# manual4.net
KiCad netlist of a schematic drawn in EAGLE
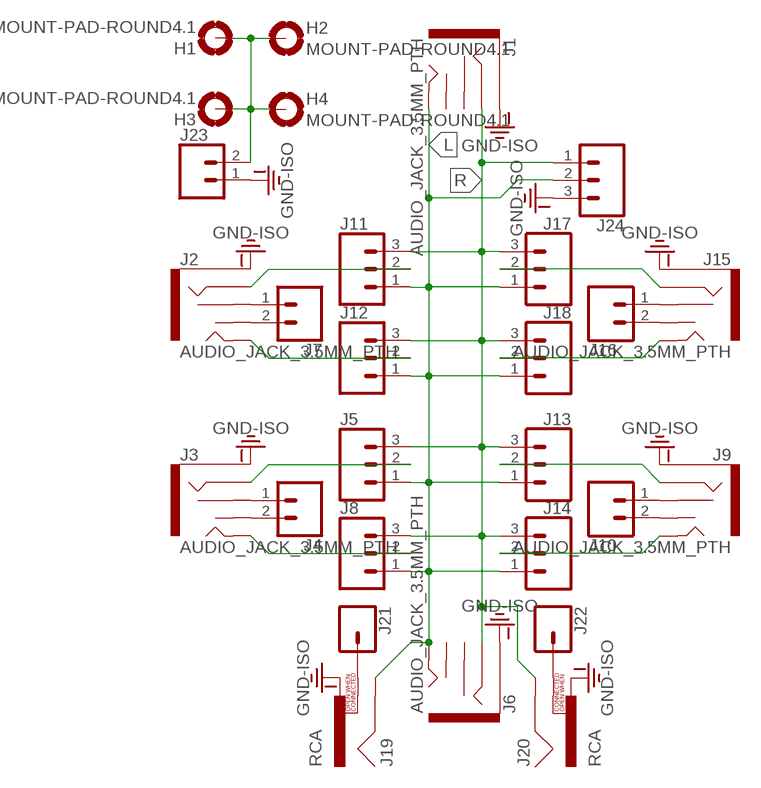
[diagram p0: schematic, sheet 1]

(export (version "E")
  (design (tool "Eeschema 10.0.6"))
  (components
    (comp (ref "H1")
      (value "MOUNT-PAD-ROUND4.1")
      (footprint "eagle-import:4,1-PAD")
      (libsource (lib "eagle-import") (part "MOUNT-PAD-ROUND4.1"))
    )
    (comp (ref "H2")
      (value "MOUNT-PAD-ROUND4.1")
      (footprint "eagle-import:4,1-PAD")
      (libsource (lib "eagle-import") (part "MOUNT-PAD-ROUND4.1"))
    )
    (comp (ref "H3")
      (value "MOUNT-PAD-ROUND4.1")
      (footprint "eagle-import:4,1-PAD")
      (libsource (lib "eagle-import") (part "MOUNT-PAD-ROUND4.1"))
    )
    (comp (ref "H4")
      (value "MOUNT-PAD-ROUND4.1")
      (footprint "eagle-import:4,1-PAD")
      (libsource (lib "eagle-import") (part "MOUNT-PAD-ROUND4.1"))
    )
    (comp (ref "J1")
      (value "AUDIO_JACK_3.5MM_PTH")
      (footprint "eagle-import:AUDIO-JACK")
      (libsource (lib "eagle-import") (part "AUDIO_JACK_3.5MM_PTH"))
    )
    (comp (ref "J2")
      (value "AUDIO_JACK_3.5MM_PTH")
      (footprint "eagle-import:AUDIO-JACK")
      (libsource (lib "eagle-import") (part "AUDIO_JACK_3.5MM_PTH"))
    )
    (comp (ref "J3")
      (value "AUDIO_JACK_3.5MM_PTH")
      (footprint "eagle-import:AUDIO-JACK")
      (libsource (lib "eagle-import") (part "AUDIO_JACK_3.5MM_PTH"))
    )
    (comp (ref "J4")
      (value "CONN_02")
      (footprint "eagle-import:1X02")
      (libsource (lib "eagle-import") (part "CONN_02"))
    )
    (comp (ref "J5")
      (value "CONN_03")
      (footprint "eagle-import:1X03")
      (libsource (lib "eagle-import") (part "CONN_03"))
    )
    (comp (ref "J6")
      (value "AUDIO_JACK_3.5MM_PTH")
      (footprint "eagle-import:AUDIO-JACK")
      (libsource (lib "eagle-import") (part "AUDIO_JACK_3.5MM_PTH"))
    )
    (comp (ref "J7")
      (value "CONN_02")
      (footprint "eagle-import:1X02")
      (libsource (lib "eagle-import") (part "CONN_02"))
    )
    (comp (ref "J8")
      (value "CONN_03")
      (footprint "eagle-import:1X03")
      (libsource (lib "eagle-import") (part "CONN_03"))
    )
    (comp (ref "J9")
      (value "AUDIO_JACK_3.5MM_PTH")
      (footprint "eagle-import:AUDIO-JACK")
      (libsource (lib "eagle-import") (part "AUDIO_JACK_3.5MM_PTH"))
    )
    (comp (ref "J10")
      (value "CONN_02")
      (footprint "eagle-import:1X02")
      (libsource (lib "eagle-import") (part "CONN_02"))
    )
    (comp (ref "J11")
      (value "CONN_03")
      (footprint "eagle-import:1X03")
      (libsource (lib "eagle-import") (part "CONN_03"))
    )
    (comp (ref "J12")
      (value "CONN_03")
      (footprint "eagle-import:1X03")
      (libsource (lib "eagle-import") (part "CONN_03"))
    )
    (comp (ref "J13")
      (value "CONN_03")
      (footprint "eagle-import:1X03")
      (libsource (lib "eagle-import") (part "CONN_03"))
    )
    (comp (ref "J14")
      (value "CONN_03")
      (footprint "eagle-import:1X03")
      (libsource (lib "eagle-import") (part "CONN_03"))
    )
    (comp (ref "J15")
      (value "AUDIO_JACK_3.5MM_PTH")
      (footprint "eagle-import:AUDIO-JACK")
      (libsource (lib "eagle-import") (part "AUDIO_JACK_3.5MM_PTH"))
    )
    (comp (ref "J16")
      (value "CONN_02")
      (footprint "eagle-import:1X02")
      (libsource (lib "eagle-import") (part "CONN_02"))
    )
    (comp (ref "J17")
      (value "CONN_03")
      (footprint "eagle-import:1X03")
      (libsource (lib "eagle-import") (part "CONN_03"))
    )
    (comp (ref "J18")
      (value "CONN_03")
      (footprint "eagle-import:1X03")
      (libsource (lib "eagle-import") (part "CONN_03"))
    )
    (comp (ref "J19")
      (value "RCA")
      (footprint "eagle-import:RCA")
      (libsource (lib "eagle-import") (part "RCA"))
    )
    (comp (ref "J20")
      (value "RCA")
      (footprint "eagle-import:RCA")
      (libsource (lib "eagle-import") (part "RCA"))
    )
    (comp (ref "J21")
      (value "CONN_01")
      (footprint "eagle-import:1X01")
      (libsource (lib "eagle-import") (part "CONN_01"))
    )
    (comp (ref "J22")
      (value "CONN_01")
      (footprint "eagle-import:1X01")
      (libsource (lib "eagle-import") (part "CONN_01"))
    )
    (comp (ref "J23")
      (value "CONN_02")
      (footprint "eagle-import:1X02")
      (libsource (lib "eagle-import") (part "CONN_02"))
    )
    (comp (ref "J24")
      (value "CONN_03")
      (footprint "eagle-import:1X03")
      (libsource (lib "eagle-import") (part "CONN_03"))
    )
  )
  (nets
    (net (code "1") (name "GND-ISO") (class "Default")
      (node (ref "J1") (pin "SLEEVE") (pinfunction "SLEEVE_SLEEVE") (pintype "bidirectional"))
      (node (ref "J15") (pin "SLEEVE") (pinfunction "SLEEVE_SLEEVE") (pintype "bidirectional"))
      (node (ref "J19") (pin "PIN") (pinfunction "PIN_PIN") (pintype "bidirectional"))
      (node (ref "J2") (pin "SLEEVE") (pinfunction "SLEEVE_SLEEVE") (pintype "bidirectional"))
      (node (ref "J20") (pin "PIN") (pinfunction "PIN_PIN") (pintype "bidirectional"))
      (node (ref "J23") (pin "1") (pinfunction "1_1") (pintype "passive"))
      (node (ref "J24") (pin "3") (pinfunction "3_3") (pintype "passive"))
      (node (ref "J3") (pin "SLEEVE") (pinfunction "SLEEVE_SLEEVE") (pintype "bidirectional"))
      (node (ref "J6") (pin "SLEEVE") (pinfunction "SLEEVE_SLEEVE") (pintype "bidirectional"))
      (node (ref "J9") (pin "SLEEVE") (pinfunction "SLEEVE_SLEEVE") (pintype "bidirectional"))
    )
    (net (code "2") (name "L") (class "Default")
      (node (ref "J1") (pin "TIP") (pinfunction "TIP_TIP") (pintype "bidirectional"))
      (node (ref "J11") (pin "1") (pinfunction "1_1") (pintype "passive"))
      (node (ref "J12") (pin "1") (pinfunction "1_1") (pintype "passive"))
      (node (ref "J13") (pin "1") (pinfunction "1_1") (pintype "passive"))
      (node (ref "J14") (pin "1") (pinfunction "1_1") (pintype "passive"))
      (node (ref "J17") (pin "1") (pinfunction "1_1") (pintype "passive"))
      (node (ref "J18") (pin "1") (pinfunction "1_1") (pintype "passive"))
      (node (ref "J19") (pin "SHELL") (pinfunction "SHELL_SHELL") (pintype "bidirectional"))
      (node (ref "J24") (pin "2") (pinfunction "2_2") (pintype "passive"))
      (node (ref "J5") (pin "1") (pinfunction "1_1") (pintype "passive"))
      (node (ref "J6") (pin "TIP") (pinfunction "TIP_TIP") (pintype "bidirectional"))
      (node (ref "J8") (pin "1") (pinfunction "1_1") (pintype "passive"))
    )
    (net (code "3") (name "Net-(H1-MOUNT)") (class "Default")
      (node (ref "H1") (pin "B4,1") (pinfunction "MOUNT_B4,1") (pintype "passive"))
      (node (ref "H2") (pin "B4,1") (pinfunction "MOUNT_B4,1") (pintype "passive"))
      (node (ref "H3") (pin "B4,1") (pinfunction "MOUNT_B4,1") (pintype "passive"))
      (node (ref "H4") (pin "B4,1") (pinfunction "MOUNT_B4,1") (pintype "passive"))
      (node (ref "J23") (pin "2") (pinfunction "2_2") (pintype "passive"))
    )
    (net (code "4") (name "Net-(J2-PadRSH)") (class "Default")
      (node (ref "J2") (pin "RSH") (pinfunction "RSH_RSH") (pintype "bidirectional"))
      (node (ref "J7") (pin "1") (pinfunction "1_1") (pintype "passive"))
    )
    (net (code "5") (name "Net-(J2-PadTSH)") (class "Default")
      (node (ref "J2") (pin "TSH") (pinfunction "TSH_TSH") (pintype "bidirectional"))
      (node (ref "J7") (pin "2") (pinfunction "2_2") (pintype "passive"))
    )
    (net (code "6") (name "Net-(J3-PadRING)") (class "Default")
      (node (ref "J3") (pin "RING") (pinfunction "RING_RING") (pintype "bidirectional"))
      (node (ref "J5") (pin "2") (pinfunction "2_2") (pintype "passive"))
    )
    (net (code "7") (name "Net-(J3-PadRSH)") (class "Default")
      (node (ref "J3") (pin "RSH") (pinfunction "RSH_RSH") (pintype "bidirectional"))
      (node (ref "J4") (pin "1") (pinfunction "1_1") (pintype "passive"))
    )
    (net (code "8") (name "Net-(J3-PadTIP)") (class "Default")
      (node (ref "J3") (pin "TIP") (pinfunction "TIP_TIP") (pintype "bidirectional"))
      (node (ref "J8") (pin "2") (pinfunction "2_2") (pintype "passive"))
    )
    (net (code "9") (name "Net-(J3-PadTSH)") (class "Default")
      (node (ref "J3") (pin "TSH") (pinfunction "TSH_TSH") (pintype "bidirectional"))
      (node (ref "J4") (pin "2") (pinfunction "2_2") (pintype "passive"))
    )
    (net (code "10") (name "Net-(J10-Pad1)") (class "Default")
      (node (ref "J10") (pin "1") (pinfunction "1_1") (pintype "passive"))
      (node (ref "J9") (pin "RSH") (pinfunction "RSH_RSH") (pintype "bidirectional"))
    )
    (net (code "11") (name "Net-(J10-Pad2)") (class "Default")
      (node (ref "J10") (pin "2") (pinfunction "2_2") (pintype "passive"))
      (node (ref "J9") (pin "TSH") (pinfunction "TSH_TSH") (pintype "bidirectional"))
    )
    (net (code "12") (name "Net-(J11-Pad2)") (class "Default")
      (node (ref "J11") (pin "2") (pinfunction "2_2") (pintype "passive"))
      (node (ref "J2") (pin "RING") (pinfunction "RING_RING") (pintype "bidirectional"))
    )
    (net (code "13") (name "Net-(J12-Pad2)") (class "Default")
      (node (ref "J12") (pin "2") (pinfunction "2_2") (pintype "passive"))
      (node (ref "J2") (pin "TIP") (pinfunction "TIP_TIP") (pintype "bidirectional"))
    )
    (net (code "14") (name "Net-(J13-Pad2)") (class "Default")
      (node (ref "J13") (pin "2") (pinfunction "2_2") (pintype "passive"))
      (node (ref "J9") (pin "RING") (pinfunction "RING_RING") (pintype "bidirectional"))
    )
    (net (code "15") (name "Net-(J14-Pad2)") (class "Default")
      (node (ref "J14") (pin "2") (pinfunction "2_2") (pintype "passive"))
      (node (ref "J9") (pin "TIP") (pinfunction "TIP_TIP") (pintype "bidirectional"))
    )
    (net (code "16") (name "Net-(J15-PadRING)") (class "Default")
      (node (ref "J15") (pin "RING") (pinfunction "RING_RING") (pintype "bidirectional"))
      (node (ref "J17") (pin "2") (pinfunction "2_2") (pintype "passive"))
    )
    (net (code "17") (name "Net-(J15-PadRSH)") (class "Default")
      (node (ref "J15") (pin "RSH") (pinfunction "RSH_RSH") (pintype "bidirectional"))
      (node (ref "J16") (pin "1") (pinfunction "1_1") (pintype "passive"))
    )
    (net (code "18") (name "Net-(J15-PadTIP)") (class "Default")
      (node (ref "J15") (pin "TIP") (pinfunction "TIP_TIP") (pintype "bidirectional"))
      (node (ref "J18") (pin "2") (pinfunction "2_2") (pintype "passive"))
    )
    (net (code "19") (name "Net-(J15-PadTSH)") (class "Default")
      (node (ref "J15") (pin "TSH") (pinfunction "TSH_TSH") (pintype "bidirectional"))
      (node (ref "J16") (pin "2") (pinfunction "2_2") (pintype "passive"))
    )
    (net (code "20") (name "Net-(J19-PadSWITCH)") (class "Default")
      (node (ref "J19") (pin "SWITCH") (pinfunction "SWITCH_SWITCH") (pintype "bidirectional"))
      (node (ref "J21") (pin "1") (pinfunction "1_1") (pintype "passive"))
    )
    (net (code "21") (name "Net-(J20-PadSWITCH)") (class "Default")
      (node (ref "J20") (pin "SWITCH") (pinfunction "SWITCH_SWITCH") (pintype "bidirectional"))
      (node (ref "J22") (pin "1") (pinfunction "1_1") (pintype "passive"))
    )
    (net (code "22") (name "R") (class "Default")
      (node (ref "J1") (pin "RING") (pinfunction "RING_RING") (pintype "bidirectional"))
      (node (ref "J11") (pin "3") (pinfunction "3_3") (pintype "passive"))
      (node (ref "J12") (pin "3") (pinfunction "3_3") (pintype "passive"))
      (node (ref "J13") (pin "3") (pinfunction "3_3") (pintype "passive"))
      (node (ref "J14") (pin "3") (pinfunction "3_3") (pintype "passive"))
      (node (ref "J17") (pin "3") (pinfunction "3_3") (pintype "passive"))
      (node (ref "J18") (pin "3") (pinfunction "3_3") (pintype "passive"))
      (node (ref "J20") (pin "SHELL") (pinfunction "SHELL_SHELL") (pintype "bidirectional"))
      (node (ref "J24") (pin "1") (pinfunction "1_1") (pintype "passive"))
      (node (ref "J5") (pin "3") (pinfunction "3_3") (pintype "passive"))
      (node (ref "J6") (pin "RING") (pinfunction "RING_RING") (pintype "bidirectional"))
      (node (ref "J8") (pin "3") (pinfunction "3_3") (pintype "passive"))
    )
    (net (code "23") (name "unconnected-(J1-PadRSH)") (class "Default")
      (node (ref "J1") (pin "RSH") (pinfunction "RSH_RSH") (pintype "bidirectional"))
    )
    (net (code "24") (name "unconnected-(J1-PadTSH)") (class "Default")
      (node (ref "J1") (pin "TSH") (pinfunction "TSH_TSH") (pintype "bidirectional"))
    )
    (net (code "25") (name "unconnected-(J6-PadRSH)") (class "Default")
      (node (ref "J6") (pin "RSH") (pinfunction "RSH_RSH") (pintype "bidirectional"))
    )
    (net (code "26") (name "unconnected-(J6-PadTSH)") (class "Default")
      (node (ref "J6") (pin "TSH") (pinfunction "TSH_TSH") (pintype "bidirectional"))
    )
  )
)
